# 09_-_USB.net
KiCad netlist of a schematic drawn in Altium Designer
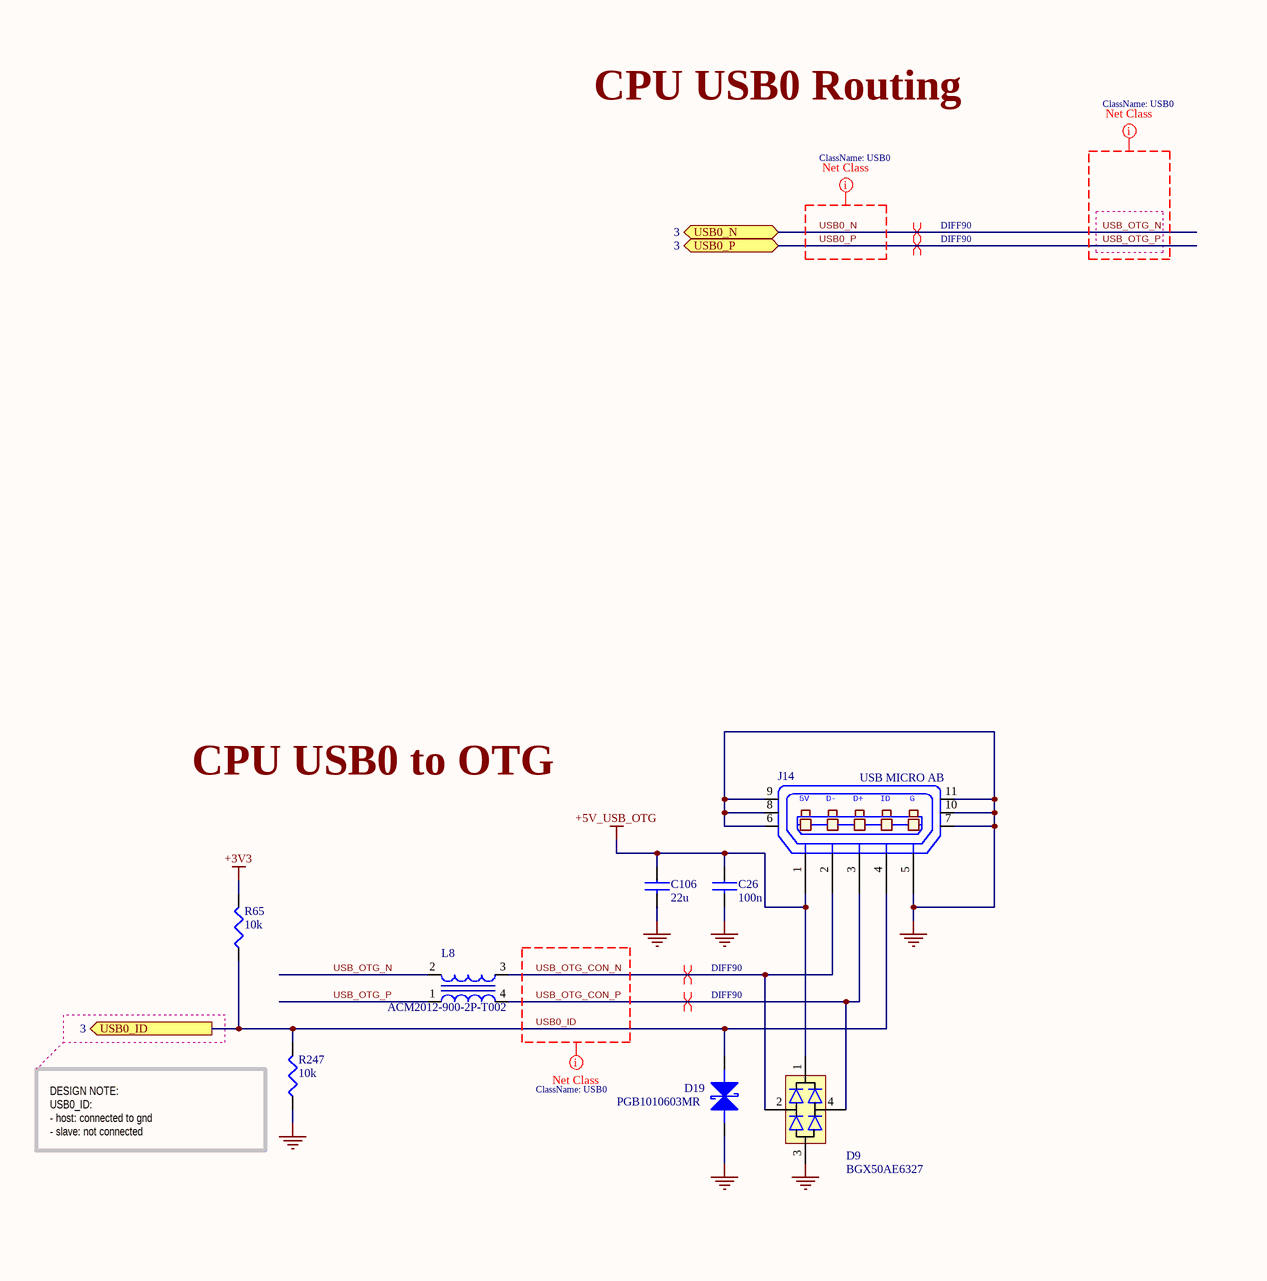
[diagram p0: [09] - USB.SchDoc, left]
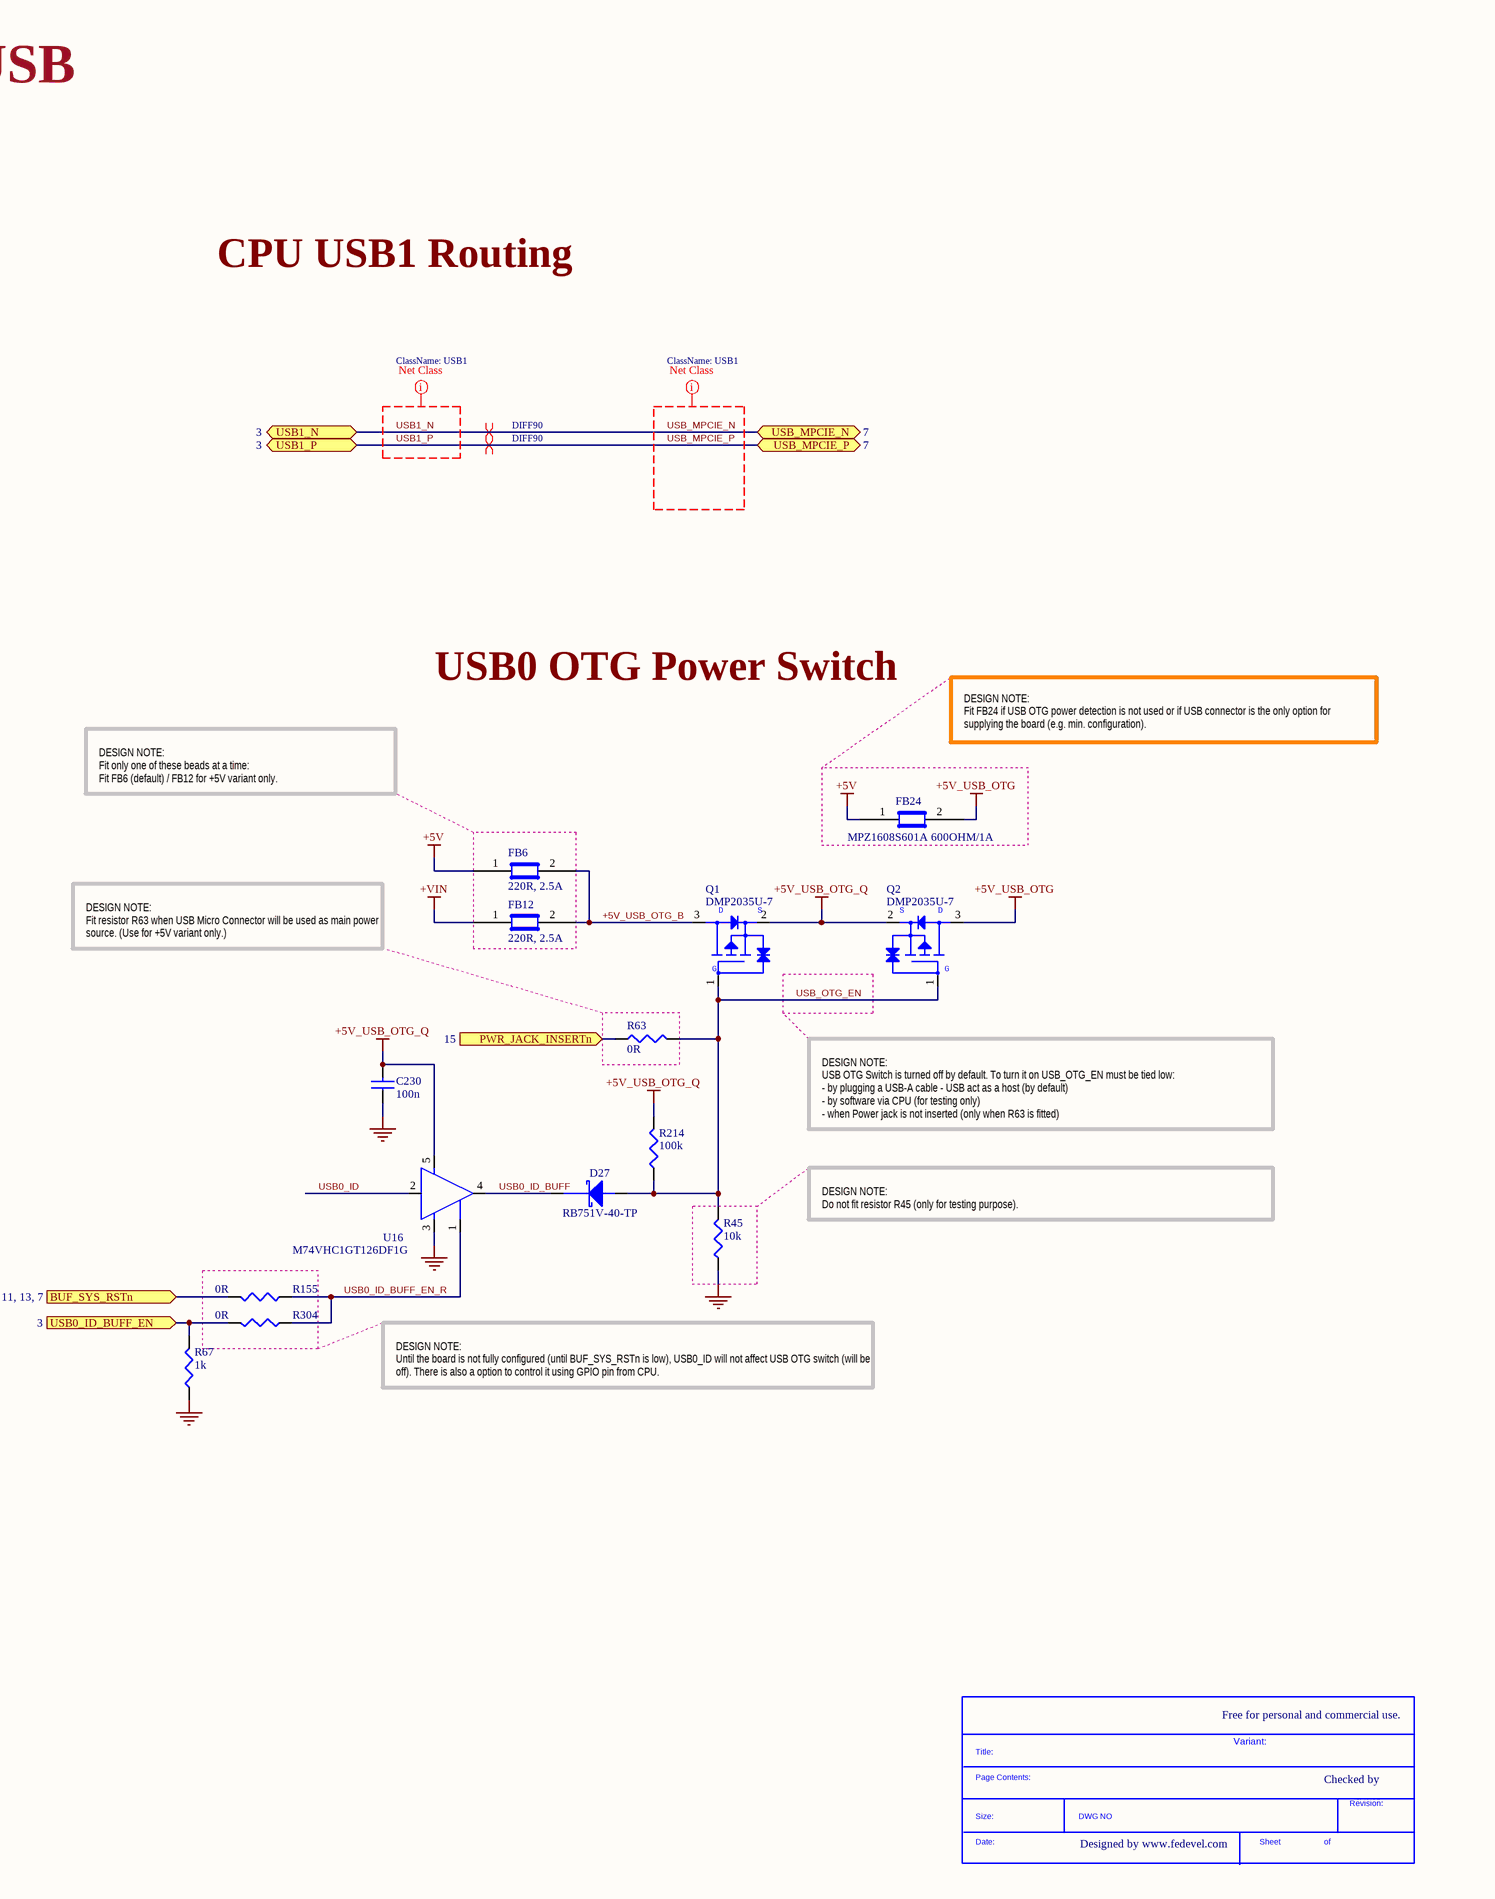
[diagram p1: [09] - USB.SchDoc, right]

(export (version "E")
  (design (tool "Eeschema 10.0.6"))
  (components
    (comp (ref "C26")
      (value "100n")
      (footprint "C0402")
      (description "CAP CER .10UF 50V X5R 10% 0402")
      (fields
        (field (name "MANUFACTURER") "TDK Corporation")
        (field (name "MANUFACTURER PART NUMBER") "C1005X5R1H104K")
      )
      (libsource (lib "Integrated_Library_FEDEVEL_APR_2015") (part "C1005X5R1H104K"))
    )
    (comp (ref "C106")
      (value "22u")
      (footprint "C0805")
      (description "CAP CER 22UF 16V 10% X5R 0805")
      (fields
        (field (name "MANUFACTURER") "TDK Corporation")
        (field (name "MANUFACTURER PART NUMBER") "C2012X5R1C226K")
        (field (name ".CHECKED PCB") "RF")
        (field (name ".CHECKED SCH") "RF")
      )
      (libsource (lib "Integrated_Library_FEDEVEL_MAY_2014") (part "C2012X5R1C226K"))
    )
    (comp (ref "C230")
      (value "100n")
      (footprint "C0402")
      (description "CAP CER .10UF 50V X5R 10% 0402")
      (fields
        (field (name "MANUFACTURER") "TDK Corporation")
        (field (name "MANUFACTURER PART NUMBER") "C1005X5R1H104K")
      )
      (libsource (lib "Integrated_Library_FEDEVEL_APR_2015") (part "C1005X5R1H104K"))
    )
    (comp (ref "D9")
      (value "BGX50AE6327")
      (footprint "SOT143")
      (description "DIODE SWITCHING 50V SOT-143")
      (fields (field (name "MANUFACTURER") "Infineon Technologies"))
      (libsource (lib "Integrated_Library_FEDEVEL_APR_2015") (part "BGX50AE6327"))
    )
    (comp (ref "D19")
      (value "PGB1010603MR")
      (footprint "C0603")
      (description "SUPPRESSOR ESD 24VDC 0603 SMD")
      (fields (field (name "MANUFACTURER") "Littelfuse Inc") (field (name ".CREATOR") "MM"))
      (libsource (lib "Integrated_Library_FEDEVEL_APR_2015") (part "PGB1010603MR"))
    )
    (comp (ref "D27")
      (value "RB751V-40-TP")
      (footprint "SOD323")
      (description "DIODE SCHTKY 30MA 30V SOD-323")
      (fields (field (name "MANUFACTURER") "Micro Commercial Co"))
      (libsource (lib "Integrated_Library_FEDEVEL_APR_2015") (part "RB751V-40-TP"))
    )
    (comp (ref "FB6")
      (value "220R, 2.5A")
      (footprint "C0603")
      (description "FERRITE CHIP 220 OHM 2500MA 0603")
      (fields
        (field (name "MANUFACTURER") "Murata Electronics North America")
        (field (name "MANUFACTURER PART NUMBER") "BLM18SG221TN1D")
      )
      (libsource (lib "Integrated_Library_FEDEVEL_APR_2015") (part "BLM18SG221TN1D"))
    )
    (comp (ref "FB12")
      (value "220R, 2.5A")
      (footprint "C0603")
      (description "FERRITE CHIP 220 OHM 2500MA 0603")
      (fields
        (field (name "MANUFACTURER") "Murata Electronics North America")
        (field (name "MANUFACTURER PART NUMBER") "BLM18SG221TN1D")
      )
      (libsource (lib "Integrated_Library_FEDEVEL_APR_2015") (part "BLM18SG221TN1D"))
    )
    (comp (ref "FB24")
      (value "MPZ1608S601A 600OHM/1A")
      (footprint "C0603")
      (description "FERRITE CHIP BEAD 600 OHM SMD 1A")
      (fields
        (field (name "MANUFACTURER") "TDK Corporation")
        (field (name "MANUFACTURER PART NUMBER") "MPZ1608S601A")
      )
      (libsource (lib "Integrated_Library_FEDEVEL_APR_2015") (part "MPZ1608S601A"))
    )
    (comp (ref "J14")
      (value "USB MICRO AB")
      (footprint "USB_Micro_AB")
      (description "CONN RCPT MICRO USB AB R/A SMD")
      (fields
        (field (name "MANUFACTURER") "Molex Inc")
        (field (name "MANUFACTURER PART NUMBER") "0475890001")
        (field (name ".CREATOR") "MM")
      )
      (libsource (lib "Integrated_Library_FEDEVEL_APR_2015") (part "0475890001"))
    )
    (comp (ref "L8")
      (value "ACM2012-900-2P-T002")
      (footprint "ACM2012")
      (description "CHOKE COMM MODE 90 OHM .4A SMD")
      (fields (field (name "MANUFACTURER") "TDK Corporation") (field (name "TOLERANCE") "±1%"))
      (libsource (lib "iMX6 TinyRex Baseboard Lite_V1I1") (part "ACM2012-900-2P-T002"))
    )
    (comp (ref "Q1")
      (value "DMP2035U-7")
      (footprint "SOT-23-3-123")
      (description "MOSFET P-CH 20V 3.6A SOT-23")
      (fields
        (field (name "MANUFACTURER") "Diodes Incorporated")
        (field (name ".CHECKED PCB") "MM")
        (field (name ".CHECKED SCH") "MM")
        (field (name ".CREATOR") "MM")
      )
      (libsource (lib "Integrated_Library_FEDEVEL_APR_2015") (part "DMP2035U-7"))
    )
    (comp (ref "Q2")
      (value "DMP2035U-7")
      (footprint "SOT-23-3-123")
      (description "MOSFET P-CH 20V 3.6A SOT-23")
      (fields
        (field (name "MANUFACTURER") "Diodes Incorporated")
        (field (name ".CHECKED PCB") "MM")
        (field (name ".CHECKED SCH") "MM")
        (field (name ".CREATOR") "MM")
      )
      (libsource (lib "Integrated_Library_FEDEVEL_APR_2015") (part "DMP2035U-7"))
    )
    (comp (ref "R45")
      (value "10k")
      (footprint "R0402")
      (description "RES 10.0K OHM 1/16W 1% 0402 SMD")
      (fields
        (field (name "MANUFACTURER") "Yageo")
        (field (name "MANUFACTURER PART NUMBER") "RC0402FR-0710KL")
      )
      (libsource (lib "Integrated_Library_FEDEVEL_APR_2015") (part "RC0402FR-0710KL"))
    )
    (comp (ref "R63")
      (value "0R")
      (footprint "R0402")
      (description "RES 0.0 OHM 1/16W 0402 SMD")
      (fields
        (field (name "MANUFACTURER") "Yageo")
        (field (name "MANUFACTURER PART NUMBER") "RC0402JR-070RL")
      )
      (libsource (lib "Integrated_Library_FEDEVEL_APR_2015") (part "RC0402JR-070RL"))
    )
    (comp (ref "R65")
      (value "10k")
      (footprint "R0402")
      (description "RES 10.0K OHM 1/16W 1% 0402 SMD")
      (fields
        (field (name "MANUFACTURER") "Yageo")
        (field (name "MANUFACTURER PART NUMBER") "RC0402FR-0710KL")
      )
      (libsource (lib "Integrated_Library_FEDEVEL_APR_2015") (part "RC0402FR-0710KL"))
    )
    (comp (ref "R67")
      (value "1k")
      (footprint "R0402")
      (description "RES 1.00K OHM 1/16W 1% 0402 SMD")
      (fields
        (field (name "MANUFACTURER") "Yageo")
        (field (name "MANUFACTURER PART NUMBER") "RC0402FR-071KL")
      )
      (libsource (lib "Integrated_Library_FEDEVEL_APR_2015") (part "RC0402FR-071KL"))
    )
    (comp (ref "R155")
      (value "0R")
      (footprint "R0402")
      (description "RES 0.0 OHM 1/16W 0402 SMD")
      (fields
        (field (name "MANUFACTURER") "Yageo")
        (field (name "MANUFACTURER PART NUMBER") "RC0402JR-070RL")
      )
      (libsource (lib "Integrated_Library_FEDEVEL_APR_2015") (part "RC0402JR-070RL"))
    )
    (comp (ref "R214")
      (value "100k")
      (footprint "R0402")
      (description "RES 100K OHM 1/16W 1% 0402 SMD")
      (fields
        (field (name "MANUFACTURER") "Stackpole Electronics Inc")
        (field (name "MANUFACTURER PART NUMBER") "RMCF0402FT100K")
      )
      (libsource (lib "Integrated_Library_FEDEVEL_APR_2015") (part "RMCF0402FT100K"))
    )
    (comp (ref "R247")
      (value "10k")
      (footprint "R0402")
      (description "RES 10.0K OHM 1/16W 1% 0402 SMD")
      (fields
        (field (name "MANUFACTURER") "Yageo")
        (field (name "MANUFACTURER PART NUMBER") "RC0402FR-0710KL")
      )
      (libsource (lib "Integrated_Library_FEDEVEL_APR_2015") (part "RC0402FR-0710KL"))
    )
    (comp (ref "R304")
      (value "0R")
      (footprint "R0402")
      (description "RES 0.0 OHM 1/16W 0402 SMD")
      (fields
        (field (name "MANUFACTURER") "Yageo")
        (field (name "MANUFACTURER PART NUMBER") "RC0402JR-070RL")
      )
      (libsource (lib "Integrated_Library_FEDEVEL_APR_2015") (part "RC0402JR-070RL"))
    )
    (comp (ref "U16")
      (value "M74VHC1GT126DF1G")
      (footprint "SC70_5")
      (description "IC BUFF CMOS LVL/SFTR N-I SOT353")
      (fields
        (field (name "MANUFACTURER") "ON Semiconductor")
        (field (name ".CHECKED PCB") "MM")
        (field (name ".CHECKED SCH") "MM")
        (field (name ".CREATOR") "MM")
      )
      (libsource (lib "Integrated_Library_FEDEVEL_APR_2015") (part "M74VHC1GT126DF1G"))
    )
  )
  (nets
    (net (code "1") (name "+3V3") (class "Default")
      (node (ref "R65") (pin "2") (pinfunction "2_2") (pintype "passive"))
    )
    (net (code "2") (name "+5V") (class "Default")
      (node (ref "FB24") (pin "1") (pinfunction "1_1") (pintype "passive"))
      (node (ref "FB6") (pin "1") (pinfunction "1_1") (pintype "passive"))
    )
    (net (code "3") (name "+5V_USB_OTG") (class "Default")
      (node (ref "C106") (pin "1") (pinfunction "1_1") (pintype "passive"))
      (node (ref "C26") (pin "1") (pinfunction "1_1") (pintype "passive"))
      (node (ref "D9") (pin "1") (pinfunction "1_1") (pintype "passive"))
      (node (ref "FB24") (pin "2") (pinfunction "2_2") (pintype "passive"))
      (node (ref "J14") (pin "1") (pinfunction "P1_1") (pintype "passive"))
      (node (ref "Q2") (pin "3") (pinfunction "3_3") (pintype "passive"))
    )
    (net (code "4") (name "+5V_USB_OTG_Q") (class "Default")
      (node (ref "C230") (pin "2") (pinfunction "2_2") (pintype "passive"))
      (node (ref "Q1") (pin "2") (pinfunction "2_2") (pintype "passive"))
      (node (ref "Q2") (pin "2") (pinfunction "2_2") (pintype "passive"))
      (node (ref "R214") (pin "2") (pinfunction "2_2") (pintype "passive"))
      (node (ref "U16") (pin "5") (pinfunction "VCC_5") (pintype "power_in"))
    )
    (net (code "5") (name "+VIN") (class "Default")
      (node (ref "FB12") (pin "1") (pinfunction "1_1") (pintype "passive"))
    )
    (net (code "6") (name "/+5V_USB_OTG_B") (class "Default")
      (node (ref "FB12") (pin "2") (pinfunction "2_2") (pintype "passive"))
      (node (ref "FB6") (pin "2") (pinfunction "2_2") (pintype "passive"))
      (node (ref "Q1") (pin "3") (pinfunction "3_3") (pintype "passive"))
    )
    (net (code "7") (name "/BUF_SYS_RSTn") (class "Default")
      (node (ref "R155") (pin "2") (pinfunction "2_2") (pintype "passive"))
    )
    (net (code "8") (name "/PWR_JACK_INSERTn") (class "Default")
      (node (ref "R63") (pin "1") (pinfunction "1_1") (pintype "passive"))
    )
    (net (code "9") (name "/USB0_ID") (class "Default")
      (node (ref "D19") (pin "1") (pinfunction "1_1") (pintype "passive"))
      (node (ref "J14") (pin "4") (pinfunction "P4_4") (pintype "passive"))
      (node (ref "R247") (pin "2") (pinfunction "2_2") (pintype "passive"))
      (node (ref "R65") (pin "1") (pinfunction "1_1") (pintype "passive"))
      (node (ref "U16") (pin "2") (pinfunction "I_2") (pintype "passive"))
    )
    (net (code "10") (name "/USB0_ID_BUFF") (class "Default")
      (node (ref "D27") (pin "1") (pinfunction "cathode_1") (pintype "passive"))
      (node (ref "U16") (pin "4") (pinfunction "O_4") (pintype "tri_state"))
    )
    (net (code "11") (name "/USB0_ID_BUFF_EN") (class "Default")
      (node (ref "R304") (pin "2") (pinfunction "2_2") (pintype "passive"))
      (node (ref "R67") (pin "2") (pinfunction "2_2") (pintype "passive"))
    )
    (net (code "12") (name "/USB0_ID_BUFF_EN_R") (class "Default")
      (node (ref "R155") (pin "1") (pinfunction "1_1") (pintype "passive"))
      (node (ref "R304") (pin "1") (pinfunction "1_1") (pintype "passive"))
      (node (ref "U16") (pin "1") (pinfunction "OE#_1") (pintype "passive"))
    )
    (net (code "13") (name "/USB0_N") (class "Default")
      (node (ref "L8") (pin "2") (pinfunction "2_2") (pintype "passive"))
    )
    (net (code "14") (name "/USB0_P") (class "Default")
      (node (ref "L8") (pin "1") (pinfunction "1_1") (pintype "passive"))
    )
    (net (code "17") (name "/USB_OTG_CON_N") (class "Default")
      (node (ref "D9") (pin "2") (pinfunction "2_2") (pintype "passive"))
      (node (ref "J14") (pin "2") (pinfunction "P2_2") (pintype "passive"))
      (node (ref "L8") (pin "3") (pinfunction "3_3") (pintype "passive"))
    )
    (net (code "18") (name "/USB_OTG_CON_P") (class "Default")
      (node (ref "D9") (pin "4") (pinfunction "4_4") (pintype "passive"))
      (node (ref "J14") (pin "3") (pinfunction "P3_3") (pintype "passive"))
      (node (ref "L8") (pin "4") (pinfunction "4_4") (pintype "passive"))
    )
    (net (code "19") (name "/USB_OTG_EN") (class "Default")
      (node (ref "D27") (pin "2") (pinfunction "ANODE_2") (pintype "passive"))
      (node (ref "Q1") (pin "1") (pinfunction "1_1") (pintype "passive"))
      (node (ref "Q2") (pin "1") (pinfunction "1_1") (pintype "passive"))
      (node (ref "R214") (pin "1") (pinfunction "1_1") (pintype "passive"))
      (node (ref "R45") (pin "2") (pinfunction "2_2") (pintype "passive"))
      (node (ref "R63") (pin "2") (pinfunction "2_2") (pintype "passive"))
    )
    (net (code "20") (name "GND") (class "Default")
      (node (ref "C106") (pin "2") (pinfunction "2_2") (pintype "passive"))
      (node (ref "C230") (pin "1") (pinfunction "1_1") (pintype "passive"))
      (node (ref "C26") (pin "2") (pinfunction "2_2") (pintype "passive"))
      (node (ref "D19") (pin "2") (pinfunction "2_2") (pintype "passive"))
      (node (ref "D9") (pin "3") (pinfunction "3_3") (pintype "passive"))
      (node (ref "J14") (pin "10") (pinfunction "10_10") (pintype "passive"))
      (node (ref "J14") (pin "11") (pinfunction "11_11") (pintype "passive"))
      (node (ref "J14") (pin "5") (pinfunction "P5_5") (pintype "passive"))
      (node (ref "J14") (pin "6") (pinfunction "6_6") (pintype "passive"))
      (node (ref "J14") (pin "7") (pinfunction "7_7") (pintype "passive"))
      (node (ref "J14") (pin "8") (pinfunction "8_8") (pintype "passive"))
      (node (ref "J14") (pin "9") (pinfunction "9_9") (pintype "passive"))
      (node (ref "R247") (pin "1") (pinfunction "1_1") (pintype "passive"))
      (node (ref "R45") (pin "1") (pinfunction "1_1") (pintype "passive"))
      (node (ref "R67") (pin "1") (pinfunction "1_1") (pintype "passive"))
      (node (ref "U16") (pin "3") (pinfunction "GND_3") (pintype "power_in"))
    )
  )
)
